# 123.net
KiCad netlist of a schematic drawn in Altium Designer
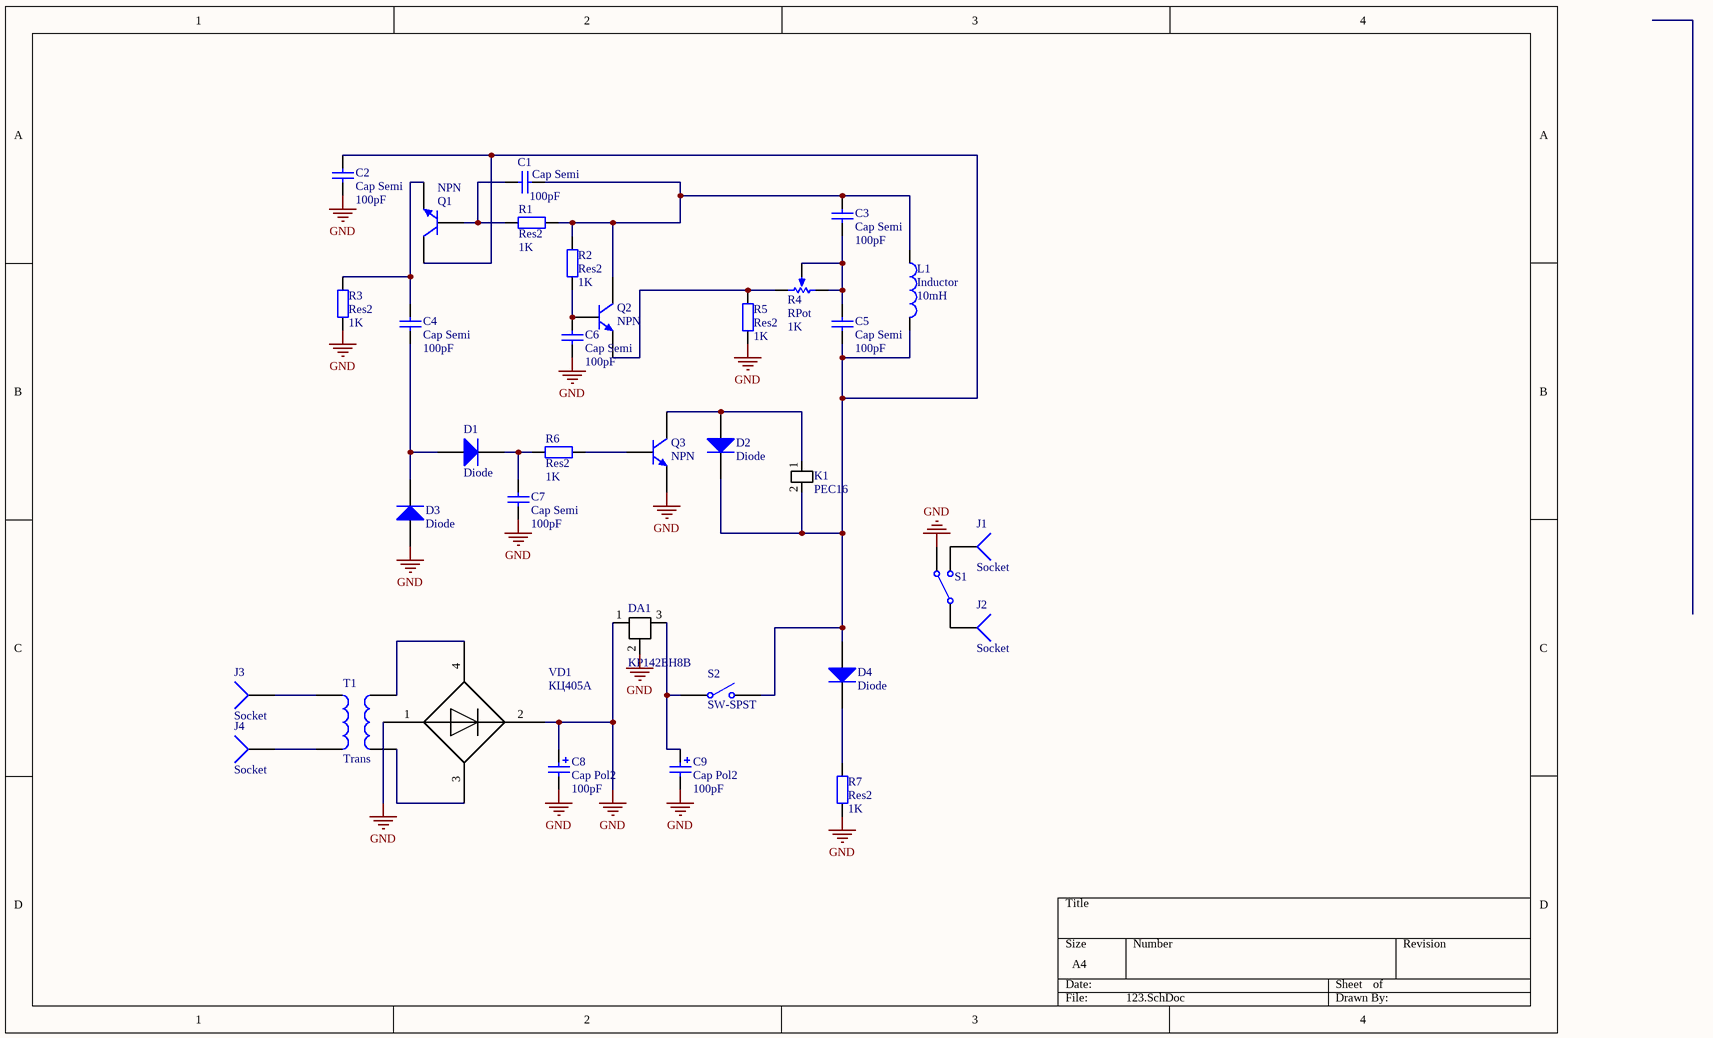
[diagram p0: 123.SchDoc]

(export (version "E")
  (design (tool "Eeschema 10.0.6"))
  (components
    (comp (ref "C1")
      (value "Cap Semi")
      (footprint "C1206")
      (description "Capacitor (Semiconductor SIM Model)")
      (fields (field (name "ALTIUM_VALUE") "100pF") (field (name "PUBLISHER") "Altium Limited"))
      (libsource (lib "Miscellaneous Devices") (part "Cap Semi"))
    )
    (comp (ref "C2")
      (value "Cap Semi")
      (footprint "C1206")
      (description "Capacitor (Semiconductor SIM Model)")
      (fields (field (name "ALTIUM_VALUE") "100pF") (field (name "PUBLISHER") "Altium Limited"))
      (libsource (lib "Miscellaneous Devices") (part "Cap Semi"))
    )
    (comp (ref "C3")
      (value "Cap Semi")
      (footprint "C1206")
      (description "Capacitor (Semiconductor SIM Model)")
      (fields (field (name "ALTIUM_VALUE") "100pF") (field (name "PUBLISHER") "Altium Limited"))
      (libsource (lib "Miscellaneous Devices") (part "Cap Semi"))
    )
    (comp (ref "C4")
      (value "Cap Semi")
      (footprint "C1206")
      (description "Capacitor (Semiconductor SIM Model)")
      (fields (field (name "ALTIUM_VALUE") "100pF") (field (name "PUBLISHER") "Altium Limited"))
      (libsource (lib "Miscellaneous Devices") (part "Cap Semi"))
    )
    (comp (ref "C5")
      (value "Cap Semi")
      (footprint "C1206")
      (description "Capacitor (Semiconductor SIM Model)")
      (fields (field (name "ALTIUM_VALUE") "100pF") (field (name "PUBLISHER") "Altium Limited"))
      (libsource (lib "Miscellaneous Devices") (part "Cap Semi"))
    )
    (comp (ref "C6")
      (value "Cap Semi")
      (footprint "C1206")
      (description "Capacitor (Semiconductor SIM Model)")
      (fields (field (name "ALTIUM_VALUE") "100pF") (field (name "PUBLISHER") "Altium Limited"))
      (libsource (lib "Miscellaneous Devices") (part "Cap Semi"))
    )
    (comp (ref "C7")
      (value "Cap Semi")
      (footprint "C1206")
      (description "Capacitor (Semiconductor SIM Model)")
      (fields (field (name "ALTIUM_VALUE") "100pF") (field (name "PUBLISHER") "Altium Limited"))
      (libsource (lib "Miscellaneous Devices") (part "Cap Semi"))
    )
    (comp (ref "C8")
      (value "Cap Pol2")
      (footprint "POLAR0.8")
      (description "Polarized Capacitor (Axial)")
      (fields (field (name "ALTIUM_VALUE") "100pF") (field (name "PUBLISHER") "Altium Limited"))
      (libsource (lib "Miscellaneous Devices") (part "Cap Pol2"))
    )
    (comp (ref "C9")
      (value "Cap Pol2")
      (footprint "POLAR0.8")
      (description "Polarized Capacitor (Axial)")
      (fields (field (name "ALTIUM_VALUE") "100pF") (field (name "PUBLISHER") "Altium Limited"))
      (libsource (lib "Miscellaneous Devices") (part "Cap Pol2"))
    )
    (comp (ref "D1")
      (value "Diode")
      (footprint "SMC")
      (description "Default Diode")
      (fields (field (name "PUBLISHER") "Altium Limited"))
      (libsource (lib "Miscellaneous Devices") (part "Diode"))
    )
    (comp (ref "D2")
      (value "Diode")
      (footprint "SMC")
      (description "Default Diode")
      (fields (field (name "PUBLISHER") "Altium Limited"))
      (libsource (lib "Miscellaneous Devices") (part "Diode"))
    )
    (comp (ref "D3")
      (value "Diode")
      (footprint "SMC")
      (description "Default Diode")
      (fields (field (name "PUBLISHER") "Altium Limited"))
      (libsource (lib "Miscellaneous Devices") (part "Diode"))
    )
    (comp (ref "D4")
      (value "Diode")
      (footprint "SMC")
      (description "Default Diode")
      (fields (field (name "PUBLISHER") "Altium Limited"))
      (libsource (lib "Miscellaneous Devices") (part "Diode"))
    )
    (comp (ref "DA1")
      (value "KP142EH8B")
      (footprint "PCBComponent_1 - duplicate")
      (libsource (lib "Schlib1") (part "KP142EH8B"))
    )
    (comp (ref "J1")
      (value "Socket")
      (footprint "PIN1")
      (fields (field (name "PUBLISHER") "Altium Limited"))
      (libsource (lib "Miscellaneous Connectors") (part "Socket"))
    )
    (comp (ref "J2")
      (value "Socket")
      (footprint "PIN1")
      (fields (field (name "PUBLISHER") "Altium Limited"))
      (libsource (lib "Miscellaneous Connectors") (part "Socket"))
    )
    (comp (ref "J3")
      (value "Socket")
      (footprint "PIN1")
      (fields (field (name "PUBLISHER") "Altium Limited"))
      (libsource (lib "Miscellaneous Connectors") (part "Socket"))
    )
    (comp (ref "J4")
      (value "Socket")
      (footprint "PIN1")
      (fields (field (name "PUBLISHER") "Altium Limited"))
      (libsource (lib "Miscellaneous Connectors") (part "Socket"))
    )
    (comp (ref "K1")
      (value "PEC16")
      (footprint "PCBComponent_1 - duplicate1")
      (libsource (lib "Schlib1") (part "PEC16"))
    )
    (comp (ref "L1")
      (value "Inductor")
      (footprint "0402-A")
      (fields (field (name "ALTIUM_VALUE") "10mH") (field (name "PUBLISHER") "Altium Limited"))
      (libsource (lib "Miscellaneous Devices") (part "Inductor"))
    )
    (comp (ref "Q1")
      (value "NPN")
      (footprint "TO-226-AA")
      (description "NPN Bipolar Transistor")
      (fields (field (name "PUBLISHER") "Altium Limited"))
      (libsource (lib "Miscellaneous Devices") (part "NPN"))
    )
    (comp (ref "Q2")
      (value "NPN")
      (footprint "TO-226-AA")
      (description "NPN Bipolar Transistor")
      (fields (field (name "PUBLISHER") "Altium Limited"))
      (libsource (lib "Miscellaneous Devices") (part "NPN"))
    )
    (comp (ref "Q3")
      (value "NPN")
      (footprint "TO-226-AA")
      (description "NPN Bipolar Transistor")
      (fields (field (name "PUBLISHER") "Altium Limited"))
      (libsource (lib "Miscellaneous Devices") (part "NPN"))
    )
    (comp (ref "R1")
      (value "Res2")
      (footprint "AXIAL-0.4")
      (description "Resistor")
      (fields (field (name "ALTIUM_VALUE") "1K") (field (name "PUBLISHER") "Altium Limited"))
      (libsource (lib "") (part "Res2_2"))
    )
    (comp (ref "R2")
      (value "Res2")
      (footprint "AXIAL-0.4")
      (description "Resistor")
      (fields (field (name "ALTIUM_VALUE") "1K") (field (name "PUBLISHER") "Altium Limited"))
      (libsource (lib "") (part "Res2_1"))
    )
    (comp (ref "R3")
      (value "Res2")
      (footprint "AXIAL-0.4")
      (description "Resistor")
      (fields (field (name "ALTIUM_VALUE") "1K") (field (name "PUBLISHER") "Altium Limited"))
      (libsource (lib "") (part "Res2_1"))
    )
    (comp (ref "R4")
      (value "RPot")
      (footprint "VR5")
      (description "Potentiometer")
      (fields (field (name "ALTIUM_VALUE") "1K") (field (name "PUBLISHER") "Altium Limited"))
      (libsource (lib "Miscellaneous Devices") (part "RPot"))
    )
    (comp (ref "R5")
      (value "Res2")
      (footprint "AXIAL-0.4")
      (description "Resistor")
      (fields (field (name "ALTIUM_VALUE") "1K") (field (name "PUBLISHER") "Altium Limited"))
      (libsource (lib "Miscellaneous Devices") (part "Res2"))
    )
    (comp (ref "R6")
      (value "Res2")
      (footprint "AXIAL-0.4")
      (description "Resistor")
      (fields (field (name "ALTIUM_VALUE") "1K") (field (name "PUBLISHER") "Altium Limited"))
      (libsource (lib "") (part "Res2_2"))
    )
    (comp (ref "R7")
      (value "Res2")
      (footprint "AXIAL-0.4")
      (description "Resistor")
      (fields (field (name "ALTIUM_VALUE") "1K") (field (name "PUBLISHER") "Altium Limited"))
      (libsource (lib "") (part "Res2_1"))
    )
    (comp (ref "S1")
      (value "Single-Pole, Double-Throw Switch")
      (libsource (lib "Simulation Generic Components") (part "SPDT SW"))
    )
    (comp (ref "S2")
      (value "SW-SPST")
      (footprint "SPST-2")
      (description "Single-Pole, Single-Throw Switch")
      (fields (field (name "PUBLISHER") "Altium Limited"))
      (libsource (lib "Miscellaneous Devices") (part "SW-SPST"))
    )
    (comp (ref "T1")
      (value "Trans")
      (footprint "TRANS")
      (description "Transformer")
      (fields (field (name "PUBLISHER") "Altium Limited"))
      (libsource (lib "Miscellaneous Devices") (part "Trans"))
    )
    (comp (ref "VD1")
      (value "КЦ405A")
      (footprint "PCBComponent_1")
      (libsource (lib "Schlib1") (part "КЦ405A"))
    )
  )
  (nets
    (net (code "1") (name "GND") (class "Default")
      (node (ref "C2") (pin "2") (pinfunction "2_2") (pintype "passive"))
      (node (ref "C6") (pin "2") (pinfunction "2_2") (pintype "passive"))
      (node (ref "C7") (pin "2") (pinfunction "2_2") (pintype "passive"))
      (node (ref "C8") (pin "1") (pinfunction "1_1") (pintype "passive"))
      (node (ref "C8") (pin "2") (pinfunction "2_2") (pintype "passive"))
      (node (ref "C9") (pin "2") (pinfunction "2_2") (pintype "passive"))
      (node (ref "D3") (pin "1") (pinfunction "A_1") (pintype "passive"))
      (node (ref "DA1") (pin "1") (pinfunction "1_1") (pintype "passive"))
      (node (ref "DA1") (pin "2") (pinfunction "2_2") (pintype "passive"))
      (node (ref "Q3") (pin "3") (pinfunction "E_3") (pintype "passive"))
      (node (ref "R3") (pin "1") (pinfunction "1_1") (pintype "passive"))
      (node (ref "R5") (pin "2") (pinfunction "2_2") (pintype "passive"))
      (node (ref "R7") (pin "1") (pinfunction "1_1") (pintype "passive"))
      (node (ref "S1") (pin "3") (pinfunction "3_3") (pintype "passive"))
      (node (ref "VD1") (pin "1") (pinfunction "1_1") (pintype "passive"))
      (node (ref "VD1") (pin "2") (pinfunction "2_2") (pintype "passive"))
    )
    (net (code "2") (name "Net-(D1-A)") (class "Default")
      (node (ref "C4") (pin "2") (pinfunction "2_2") (pintype "passive"))
      (node (ref "D1") (pin "1") (pinfunction "A_1") (pintype "passive"))
      (node (ref "D3") (pin "2") (pinfunction "K_2") (pintype "passive"))
    )
    (net (code "3") (name "Net-(D1-K)") (class "Default")
      (node (ref "C7") (pin "1") (pinfunction "1_1") (pintype "passive"))
      (node (ref "D1") (pin "2") (pinfunction "K_2") (pintype "passive"))
      (node (ref "R6") (pin "2") (pinfunction "2_2") (pintype "passive"))
    )
    (net (code "4") (name "Net-(D2-A)") (class "Default")
      (node (ref "D2") (pin "1") (pinfunction "A_1") (pintype "passive"))
      (node (ref "K1") (pin "1") (pinfunction "1_1") (pintype "passive"))
      (node (ref "Q3") (pin "1") (pinfunction "C_1") (pintype "passive"))
    )
    (net (code "5") (name "Net-(D2-K)") (class "Default")
      (node (ref "C2") (pin "1") (pinfunction "1_1") (pintype "passive"))
      (node (ref "C5") (pin "2") (pinfunction "2_2") (pintype "passive"))
      (node (ref "D2") (pin "2") (pinfunction "K_2") (pintype "passive"))
      (node (ref "D4") (pin "1") (pinfunction "A_1") (pintype "passive"))
      (node (ref "K1") (pin "2") (pinfunction "2_2") (pintype "passive"))
      (node (ref "L1") (pin "2") (pinfunction "2_2") (pintype "passive"))
      (node (ref "Q1") (pin "1") (pinfunction "C_1") (pintype "passive"))
      (node (ref "S2") (pin "2") (pinfunction "NO_2") (pintype "passive"))
    )
    (net (code "6") (name "Net-(D4-K)") (class "Default")
      (node (ref "D4") (pin "2") (pinfunction "K_2") (pintype "passive"))
      (node (ref "R7") (pin "2") (pinfunction "2_2") (pintype "passive"))
    )
    (net (code "7") (name "Net-(J1-Pad1)") (class "Default")
      (node (ref "J1") (pin "1") (pinfunction "1_1") (pintype "passive"))
      (node (ref "S1") (pin "2") (pinfunction "2_2") (pintype "passive"))
    )
    (net (code "8") (name "Net-(J2-Pad1)") (class "Default")
      (node (ref "J2") (pin "1") (pinfunction "1_1") (pintype "passive"))
      (node (ref "S1") (pin "1") (pinfunction "1_1") (pintype "passive"))
    )
    (net (code "9") (name "Net-(J3-Pad1)") (class "Default")
      (node (ref "J3") (pin "1") (pinfunction "1_1") (pintype "passive"))
      (node (ref "T1") (pin "1") (pinfunction "1_1") (pintype "passive"))
    )
    (net (code "10") (name "Net-(J4-Pad1)") (class "Default")
      (node (ref "J4") (pin "1") (pinfunction "1_1") (pintype "passive"))
      (node (ref "T1") (pin "2") (pinfunction "2_2") (pintype "passive"))
    )
    (net (code "11") (name "Net-(Q1-B)") (class "Default")
      (node (ref "C1") (pin "1") (pinfunction "1_1") (pintype "passive"))
      (node (ref "Q1") (pin "2") (pinfunction "B_2") (pintype "passive"))
      (node (ref "R1") (pin "2") (pinfunction "2_2") (pintype "passive"))
    )
    (net (code "12") (name "Net-(Q1-E)") (class "Default")
      (node (ref "C4") (pin "1") (pinfunction "1_1") (pintype "passive"))
      (node (ref "Q1") (pin "3") (pinfunction "E_3") (pintype "passive"))
      (node (ref "R3") (pin "2") (pinfunction "2_2") (pintype "passive"))
    )
    (net (code "13") (name "Net-(Q2-B)") (class "Default")
      (node (ref "C6") (pin "1") (pinfunction "1_1") (pintype "passive"))
      (node (ref "Q2") (pin "2") (pinfunction "B_2") (pintype "passive"))
      (node (ref "R2") (pin "1") (pinfunction "1_1") (pintype "passive"))
    )
    (net (code "14") (name "Net-(Q2-C)") (class "Default")
      (node (ref "C1") (pin "2") (pinfunction "2_2") (pintype "passive"))
      (node (ref "C3") (pin "1") (pinfunction "1_1") (pintype "passive"))
      (node (ref "L1") (pin "1") (pinfunction "1_1") (pintype "passive"))
      (node (ref "Q2") (pin "1") (pinfunction "C_1") (pintype "passive"))
      (node (ref "R1") (pin "1") (pinfunction "1_1") (pintype "passive"))
      (node (ref "R2") (pin "2") (pinfunction "2_2") (pintype "passive"))
    )
    (net (code "15") (name "Net-(Q2-E)") (class "Default")
      (node (ref "Q2") (pin "3") (pinfunction "E_3") (pintype "passive"))
      (node (ref "R4") (pin "2") (pinfunction "BOT_2") (pintype "passive"))
      (node (ref "R5") (pin "1") (pinfunction "1_1") (pintype "passive"))
    )
    (net (code "16") (name "Net-(Q3-B)") (class "Default")
      (node (ref "Q3") (pin "2") (pinfunction "B_2") (pintype "passive"))
      (node (ref "R6") (pin "1") (pinfunction "1_1") (pintype "passive"))
    )
    (net (code "17") (name "Net-(R4-TAP)") (class "Default")
      (node (ref "C3") (pin "2") (pinfunction "2_2") (pintype "passive"))
      (node (ref "C5") (pin "1") (pinfunction "1_1") (pintype "passive"))
      (node (ref "R4") (pin "1") (pinfunction "TOP_1") (pintype "passive"))
      (node (ref "R4") (pin "3") (pinfunction "TAP_3") (pintype "passive"))
    )
    (net (code "18") (name "Net-(S2-COMMON)") (class "Default")
      (node (ref "C9") (pin "1") (pinfunction "1_1") (pintype "passive"))
      (node (ref "DA1") (pin "3") (pinfunction "3_3") (pintype "passive"))
      (node (ref "S2") (pin "1") (pinfunction "COMMON_1") (pintype "passive"))
    )
    (net (code "19") (name "Net-(T1-Pad3)") (class "Default")
      (node (ref "T1") (pin "3") (pinfunction "3_3") (pintype "passive"))
      (node (ref "VD1") (pin "4") (pinfunction "4_4") (pintype "passive"))
    )
    (net (code "20") (name "Net-(T1-Pad4)") (class "Default")
      (node (ref "T1") (pin "4") (pinfunction "4_4") (pintype "passive"))
      (node (ref "VD1") (pin "3") (pinfunction "3_3") (pintype "passive"))
    )
  )
)
